# ESP32-S3_4_2_EINK_V1_3.net
KiCad netlist of a schematic drawn in EAGLE
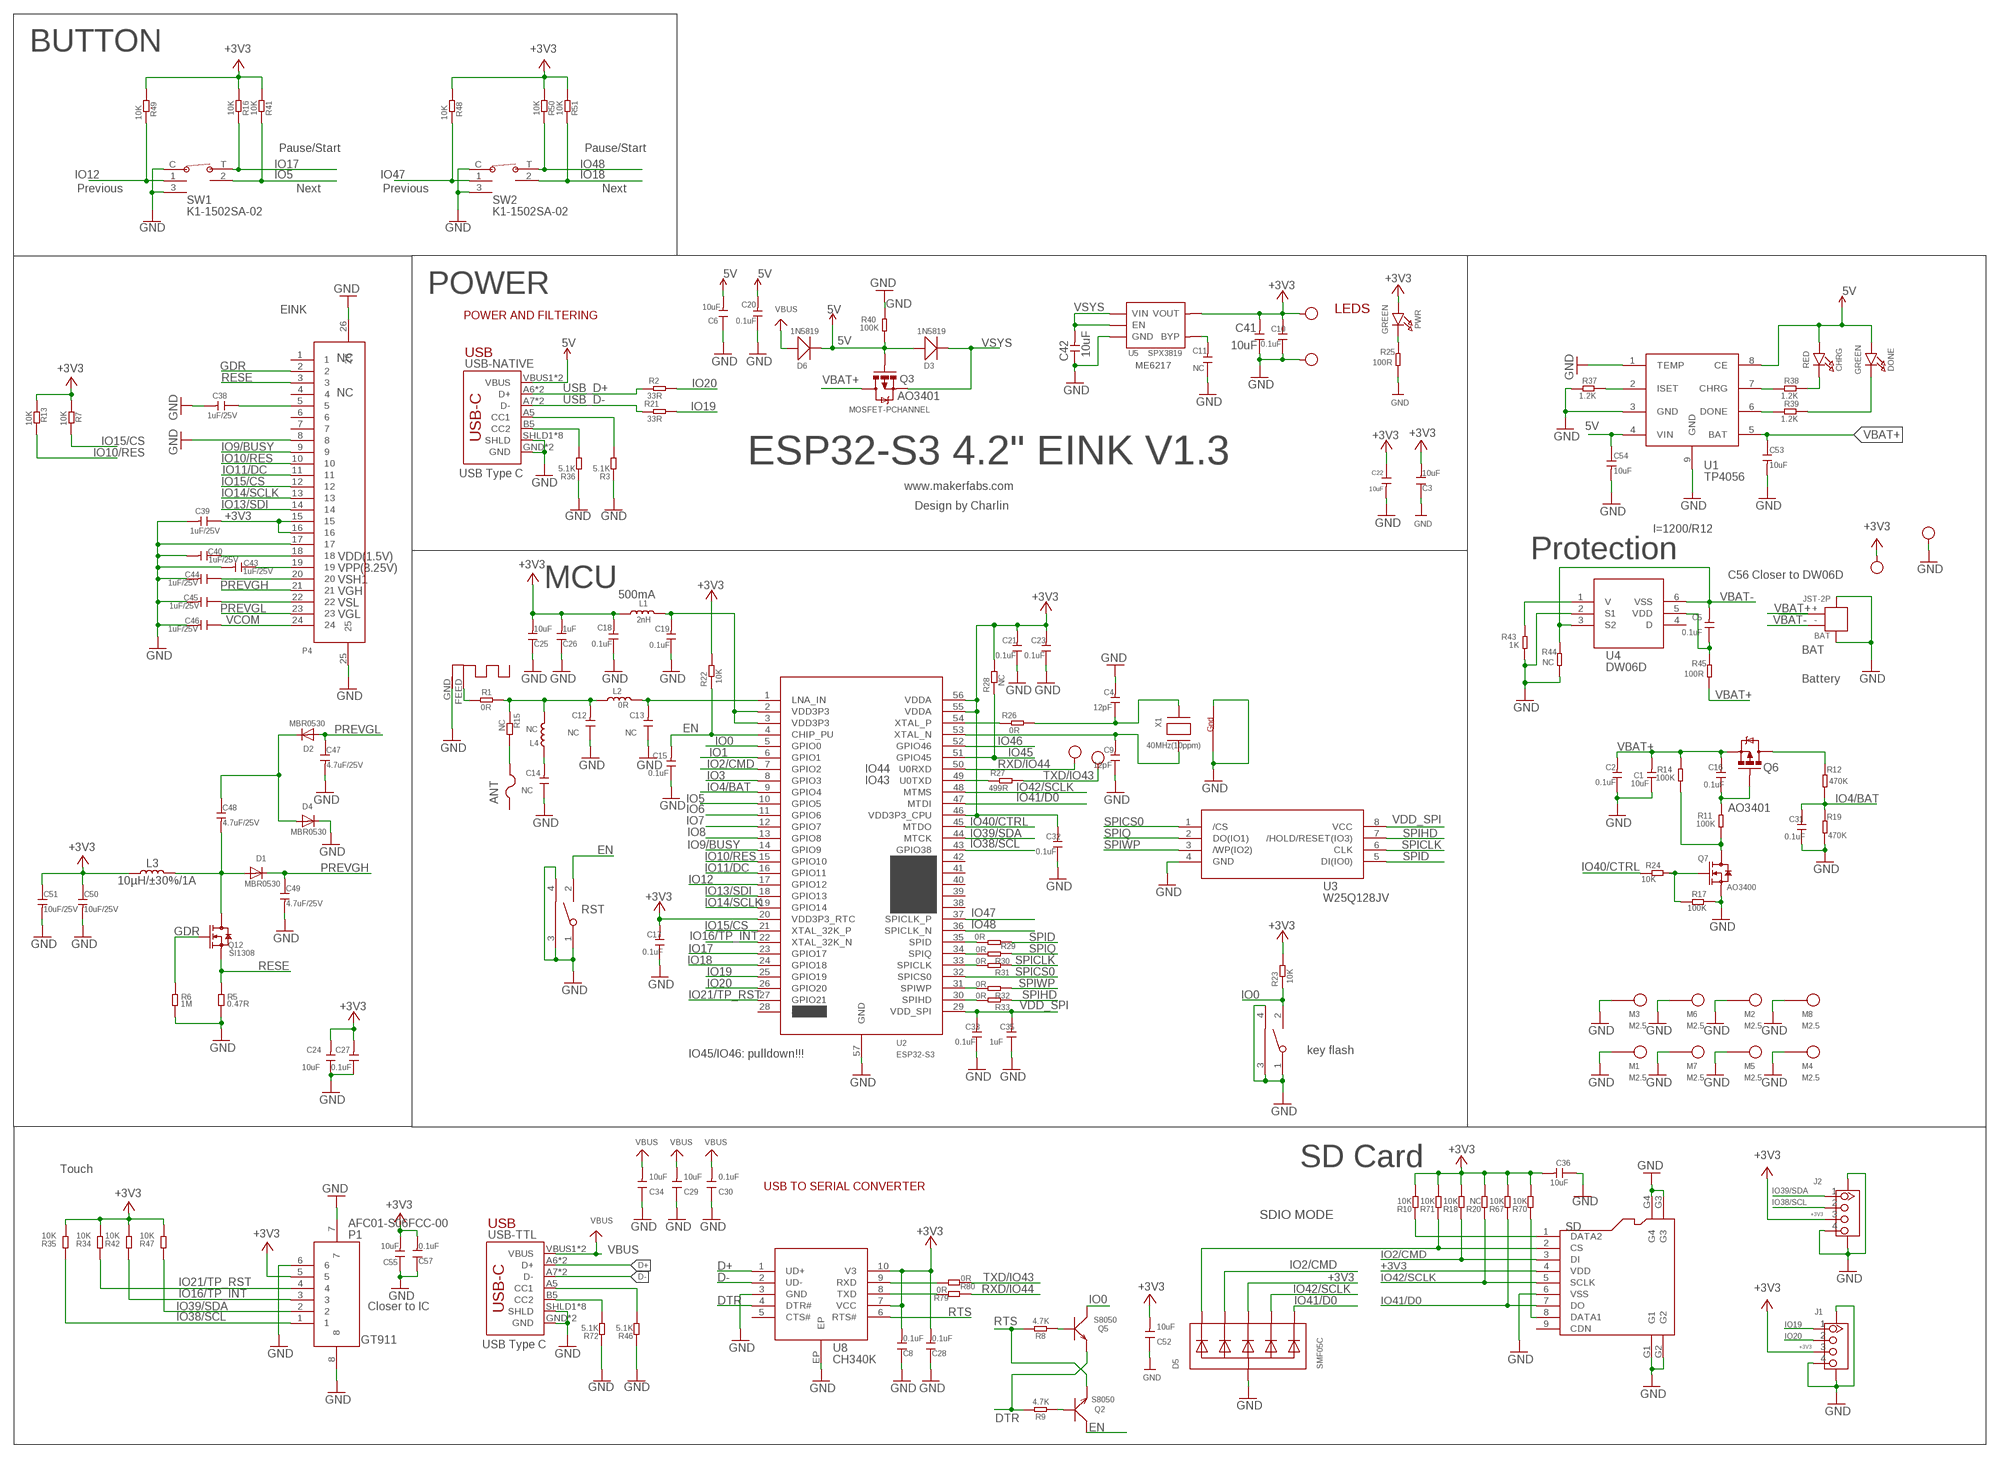
[diagram p0: schematic, sheet 1]

(export (version "E")
  (design (tool "Eeschema 10.0.6"))
  (components
    (comp (ref "3V3")
      (value "TEST-POINT'4545'")
      (footprint "eagle-import:TP-D45MIL")
      (fields (field (name "PARTNO") "DNP") (field (name "PARTNO_1") "DNP"))
      (libsource (lib "eagle-import") (part "TEST-POINT'4545'"))
    )
    (comp (ref "ANT")
      (value "PTCFUSE-1206")
      (footprint "eagle-import:R1206")
      (libsource (lib "eagle-import") (part "PTCFUSE-1206"))
    )
    (comp (ref "ANT1")
      (value "ANTENNA")
      (footprint "eagle-import:RN-ANT")
      (libsource (lib "eagle-import") (part "ANTENNA"))
    )
    (comp (ref "BAT")
      (value "JST-2P")
      (footprint "eagle-import:HW2-SMD-2.0-90D")
      (libsource (lib "eagle-import") (part "JST-2P-SMD'2.0'"))
    )
    (comp (ref "C1")
      (value "10uF")
      (footprint "eagle-import:0603")
      (libsource (lib "eagle-import") (part "C-0603"))
    )
    (comp (ref "C2")
      (value "0.1uF")
      (footprint "eagle-import:0603")
      (libsource (lib "eagle-import") (part "C-0603"))
    )
    (comp (ref "C3")
      (value "10uF")
      (footprint "eagle-import:DISCRETE_C0603")
      (libsource (lib "eagle-import") (part "DISCRETE_C-0603"))
    )
    (comp (ref "C4")
      (value "12pF")
      (footprint "eagle-import:0603")
      (libsource (lib "eagle-import") (part "C-0603"))
    )
    (comp (ref "C5")
      (value "0.1uF")
      (footprint "eagle-import:0603")
      (libsource (lib "eagle-import") (part "C-0603"))
    )
    (comp (ref "C6")
      (value "10uF")
      (footprint "eagle-import:DISCRETE_C0603")
      (libsource (lib "eagle-import") (part "DISCRETE_C-0603"))
    )
    (comp (ref "C8")
      (value "0.1uF")
      (footprint "eagle-import:DISCRETE_C0603")
      (libsource (lib "eagle-import") (part "DISCRETE_C-0603"))
    )
    (comp (ref "C9")
      (value "12pF")
      (footprint "eagle-import:0603")
      (libsource (lib "eagle-import") (part "C-0603"))
    )
    (comp (ref "C10")
      (value "0.1uF")
      (footprint "eagle-import:0603")
      (libsource (lib "eagle-import") (part "C-0603"))
    )
    (comp (ref "C11")
      (value "NC")
      (footprint "eagle-import:0603")
      (libsource (lib "eagle-import") (part "C-0603"))
    )
    (comp (ref "C12")
      (value "NC")
      (footprint "eagle-import:0603")
      (libsource (lib "eagle-import") (part "C-0603"))
    )
    (comp (ref "C13")
      (value "NC")
      (footprint "eagle-import:0603")
      (libsource (lib "eagle-import") (part "C-0603"))
    )
    (comp (ref "C14")
      (value "NC")
      (footprint "eagle-import:0603")
      (libsource (lib "eagle-import") (part "C-0603"))
    )
    (comp (ref "C15")
      (value "0.1uF")
      (footprint "eagle-import:0603")
      (libsource (lib "eagle-import") (part "C-0603"))
    )
    (comp (ref "C16")
      (value "0.1uF")
      (footprint "eagle-import:0603")
      (libsource (lib "eagle-import") (part "C-0603"))
    )
    (comp (ref "C17")
      (value "0.1uF")
      (footprint "eagle-import:0603")
      (libsource (lib "eagle-import") (part "C-0603"))
    )
    (comp (ref "C18")
      (value "0.1uF")
      (footprint "eagle-import:0603")
      (libsource (lib "eagle-import") (part "C-0603"))
    )
    (comp (ref "C19")
      (value "0.1uF")
      (footprint "eagle-import:0603")
      (libsource (lib "eagle-import") (part "C-0603"))
    )
    (comp (ref "C20")
      (value "0.1uF")
      (footprint "eagle-import:0603")
      (libsource (lib "eagle-import") (part "C-0603"))
    )
    (comp (ref "C21")
      (value "0.1uF")
      (footprint "eagle-import:0603")
      (libsource (lib "eagle-import") (part "C-0603"))
    )
    (comp (ref "C22")
      (value "10uF")
      (footprint "eagle-import:0603")
      (libsource (lib "eagle-import") (part "C-0603"))
    )
    (comp (ref "C23")
      (value "0.1uF")
      (footprint "eagle-import:0603")
      (libsource (lib "eagle-import") (part "C-0603"))
    )
    (comp (ref "C24")
      (value "10uF")
      (footprint "eagle-import:0603")
      (libsource (lib "eagle-import") (part "C-0603"))
    )
    (comp (ref "C25")
      (value "10uF")
      (footprint "eagle-import:DISCRETE_C0603")
      (libsource (lib "eagle-import") (part "DISCRETE_C-0603"))
    )
    (comp (ref "C26")
      (value "1uF")
      (footprint "eagle-import:DISCRETE_C0603")
      (libsource (lib "eagle-import") (part "DISCRETE_C-0603"))
    )
    (comp (ref "C27")
      (value "0.1uF")
      (footprint "eagle-import:0603")
      (libsource (lib "eagle-import") (part "C-0603"))
    )
    (comp (ref "C28")
      (value "0.1uF")
      (footprint "eagle-import:DISCRETE_C0603")
      (libsource (lib "eagle-import") (part "DISCRETE_C-0603"))
    )
    (comp (ref "C29")
      (value "10uF")
      (footprint "eagle-import:DISCRETE_C0603")
      (libsource (lib "eagle-import") (part "DISCRETE_C-0603"))
    )
    (comp (ref "C30")
      (value "0.1uF")
      (footprint "eagle-import:DISCRETE_C0603")
      (libsource (lib "eagle-import") (part "DISCRETE_C-0603"))
    )
    (comp (ref "C31")
      (value "0.1uF")
      (footprint "eagle-import:0603")
      (libsource (lib "eagle-import") (part "C-0603"))
    )
    (comp (ref "C32")
      (value "0.1uF")
      (footprint "eagle-import:0603")
      (libsource (lib "eagle-import") (part "C-0603"))
    )
    (comp (ref "C33")
      (value "0.1uF")
      (footprint "eagle-import:0603")
      (libsource (lib "eagle-import") (part "C-0603"))
    )
    (comp (ref "C34")
      (value "10uF")
      (footprint "eagle-import:DISCRETE_C0603")
      (libsource (lib "eagle-import") (part "DISCRETE_C-0603"))
    )
    (comp (ref "C35")
      (value "1uF")
      (footprint "eagle-import:0603")
      (libsource (lib "eagle-import") (part "C-0603"))
    )
    (comp (ref "C36")
      (value "10uF")
      (footprint "eagle-import:DISCRETE_C0603")
      (libsource (lib "eagle-import") (part "DISCRETE_C-0603"))
    )
    (comp (ref "C38")
      (value "1uF/25V")
      (footprint "eagle-import:0603")
      (libsource (lib "eagle-import") (part "C-0603"))
    )
    (comp (ref "C39")
      (value "1uF/25V")
      (footprint "eagle-import:0603")
      (libsource (lib "eagle-import") (part "C-0603"))
    )
    (comp (ref "C40")
      (value "1uF/25V")
      (footprint "eagle-import:0603")
      (libsource (lib "eagle-import") (part "C-0603"))
    )
    (comp (ref "C41")
      (value "10uF")
      (footprint "eagle-import:0603")
      (libsource (lib "eagle-import") (part "C-0603"))
    )
    (comp (ref "C42")
      (value "10uF")
      (footprint "eagle-import:0603")
      (libsource (lib "eagle-import") (part "C-0603"))
    )
    (comp (ref "C43")
      (value "1uF/25V")
      (footprint "eagle-import:0603")
      (libsource (lib "eagle-import") (part "C-0603"))
    )
    (comp (ref "C44")
      (value "1uF/25V")
      (footprint "eagle-import:0603")
      (libsource (lib "eagle-import") (part "C-0603"))
    )
    (comp (ref "C45")
      (value "1uF/25V")
      (footprint "eagle-import:0603")
      (libsource (lib "eagle-import") (part "C-0603"))
    )
    (comp (ref "C46")
      (value "1uF/25V")
      (footprint "eagle-import:0603")
      (libsource (lib "eagle-import") (part "C-0603"))
    )
    (comp (ref "C47")
      (value "4.7uF/25V")
      (footprint "eagle-import:0603")
      (libsource (lib "eagle-import") (part "C-0603"))
    )
    (comp (ref "C48")
      (value "4.7uF/25V")
      (footprint "eagle-import:0603")
      (libsource (lib "eagle-import") (part "C-0603"))
    )
    (comp (ref "C49")
      (value "4.7uF/25V")
      (footprint "eagle-import:0603")
      (libsource (lib "eagle-import") (part "C-0603"))
    )
    (comp (ref "C50")
      (value "10uF/25V")
      (footprint "eagle-import:0603")
      (libsource (lib "eagle-import") (part "C-0603"))
    )
    (comp (ref "C51")
      (value "10uF/25V")
      (footprint "eagle-import:0603")
      (libsource (lib "eagle-import") (part "C-0603"))
    )
    (comp (ref "C52")
      (value "10uF")
      (footprint "eagle-import:DISCRETE_C0603")
      (libsource (lib "eagle-import") (part "DISCRETE_C-0603"))
    )
    (comp (ref "C53")
      (value "10uF")
      (footprint "eagle-import:0603")
      (libsource (lib "eagle-import") (part "C-0603"))
    )
    (comp (ref "C54")
      (value "10uF")
      (footprint "eagle-import:0603")
      (libsource (lib "eagle-import") (part "C-0603"))
    )
    (comp (ref "C55")
      (value "10uF")
      (footprint "eagle-import:DISCRETE_C0603")
      (libsource (lib "eagle-import") (part "DISCRETE_C-0603"))
    )
    (comp (ref "C57")
      (value "0.1uF")
      (footprint "eagle-import:DISCRETE_C0603")
      (libsource (lib "eagle-import") (part "DISCRETE_C-0603"))
    )
    (comp (ref "CHRG")
      (value "RED")
      (footprint "eagle-import:CHIPLED_0805_NOOUTLINE")
      (libsource (lib "eagle-import") (part "LED0805_NOOUTLINE"))
    )
    (comp (ref "D1")
      (value "MBR0530")
      (footprint "eagle-import:SOD-323F")
      (libsource (lib "eagle-import") (part "DIODESOD-323F"))
    )
    (comp (ref "D2")
      (value "MBR0530")
      (footprint "eagle-import:SOD-323F")
      (libsource (lib "eagle-import") (part "DIODESOD-323F"))
    )
    (comp (ref "D3")
      (value "1N5819")
      (footprint "eagle-import:SOD323")
      (libsource (lib "eagle-import") (part "D'0805'"))
    )
    (comp (ref "D4")
      (value "MBR0530")
      (footprint "eagle-import:SOD-323F")
      (libsource (lib "eagle-import") (part "DIODESOD-323F"))
    )
    (comp (ref "D5")
      (value "SMF05C")
      (footprint "eagle-import:SOT363")
      (libsource (lib "eagle-import") (part "TVSARRAY_5LANE"))
    )
    (comp (ref "D6")
      (value "1N5819")
      (footprint "eagle-import:SOD323")
      (libsource (lib "eagle-import") (part "D'0805'"))
    )
    (comp (ref "DONE")
      (value "GREEN")
      (footprint "eagle-import:CHIPLED_0805_NOOUTLINE")
      (libsource (lib "eagle-import") (part "LED0805_NOOUTLINE"))
    )
    (comp (ref "FLASH")
      (value "TS24CA")
      (footprint "eagle-import:2_4_3.5MM")
      (libsource (lib "eagle-import") (part "TS24CA"))
    )
    (comp (ref "G")
      (value "TEST-POINT'4545'")
      (footprint "eagle-import:TP-D45MIL")
      (fields (field (name "PARTNO") "DNP") (field (name "PARTNO_1") "DNP"))
      (libsource (lib "eagle-import") (part "TEST-POINT'4545'"))
    )
    (comp (ref "GND")
      (value "TEST-POINT'4545'")
      (footprint "eagle-import:TP-D45MIL")
      (fields (field (name "PARTNO") "DNP") (field (name "PARTNO_1") "DNP"))
      (libsource (lib "eagle-import") (part "TEST-POINT'4545'"))
    )
    (comp (ref "J1")
      (value "GROVE-CONNECTOR-SMD'90D'")
      (footprint "eagle-import:HW4-SMD-2.0-90D")
      (libsource (lib "eagle-import") (part "GROVE-CONNECTOR-SMD'90D'"))
    )
    (comp (ref "J2")
      (value "GROVE-CONNECTOR-SMD'90D'")
      (footprint "eagle-import:HW4-SMD-2.0-90D")
      (libsource (lib "eagle-import") (part "GROVE-CONNECTOR-SMD'90D'"))
    )
    (comp (ref "L1")
      (value "2nH")
      (footprint "eagle-import:DISCRETE_L0603")
      (libsource (lib "eagle-import") (part "DISCRETE_L0603"))
    )
    (comp (ref "L2")
      (value "0R")
      (footprint "eagle-import:0603")
      (fields (field (name "PROD_ID") "NDUC-07874"))
      (libsource (lib "eagle-import") (part "INDUCTOR-0603-33NH"))
    )
    (comp (ref "L3")
      (value "10µH/±30%/1A")
      (footprint "eagle-import:CR54")
      (fields (field (name "PROD_ID") "NDUC-10789"))
      (libsource (lib "eagle-import") (part "INDUCTOR-CR54-47UH"))
    )
    (comp (ref "L4")
      (value "NC")
      (footprint "eagle-import:0603")
      (fields (field (name "PROD_ID") "NDUC-07874"))
      (libsource (lib "eagle-import") (part "INDUCTOR-0603-33NH"))
    )
    (comp (ref "M1")
      (value "M2.5")
      (footprint "eagle-import:M2.5")
      (libsource (lib "eagle-import") (part "M2.5"))
    )
    (comp (ref "M2")
      (value "M2.5")
      (footprint "eagle-import:M2.5")
      (libsource (lib "eagle-import") (part "M2.5"))
    )
    (comp (ref "M3")
      (value "M2.5")
      (footprint "eagle-import:M2.5")
      (libsource (lib "eagle-import") (part "M2.5"))
    )
    (comp (ref "M4")
      (value "M2.5")
      (footprint "eagle-import:M2.5")
      (libsource (lib "eagle-import") (part "M2.5"))
    )
    (comp (ref "M5")
      (value "M2.5")
      (footprint "eagle-import:M2.5")
      (libsource (lib "eagle-import") (part "M2.5"))
    )
    (comp (ref "M6")
      (value "M2.5")
      (footprint "eagle-import:M2.5")
      (libsource (lib "eagle-import") (part "M2.5"))
    )
    (comp (ref "M7")
      (value "M2.5")
      (footprint "eagle-import:M2.5")
      (libsource (lib "eagle-import") (part "M2.5"))
    )
    (comp (ref "M8")
      (value "M2.5")
      (footprint "eagle-import:M2.5")
      (libsource (lib "eagle-import") (part "M2.5"))
    )
    (comp (ref "P1")
      (value "AFC01-S06FCC-00")
      (footprint "eagle-import:SMD8-50P-740L535W")
      (libsource (lib "eagle-import") (part "AFC01-S06FCC-00"))
    )
    (comp (ref "P4")
      (value "FPC-24P")
      (footprint "eagle-import:SMD26-50P-1760L450W")
      (libsource (lib "eagle-import") (part "FPC-24P"))
    )
    (comp (ref "PWR")
      (value "GREEN")
      (footprint "eagle-import:CHIPLED_0805_NOOUTLINE")
      (libsource (lib "eagle-import") (part "LED0805_NOOUTLINE"))
    )
    (comp (ref "Q2")
      (value "S8050")
      (footprint "eagle-import:SOT23")
      (libsource (lib "eagle-import") (part "TRANSISTOR-NPN-SOT23"))
    )
    (comp (ref "Q3")
      (value "MOSFET-PCHANNEL")
      (footprint "eagle-import:SOT23-3")
      (libsource (lib "eagle-import") (part "MOSFET-PCHANNEL"))
    )
    (comp (ref "Q5")
      (value "S8050")
      (footprint "eagle-import:SOT23")
      (libsource (lib "eagle-import") (part "TRANSISTOR-NPN-SOT23"))
    )
    (comp (ref "Q6")
      (value "MOSFET-PCHANNEL")
      (footprint "eagle-import:SOT23-3")
      (libsource (lib "eagle-import") (part "MOSFET-PCHANNEL"))
    )
    (comp (ref "Q7")
      (value "AO3400")
      (footprint "eagle-import:DISCRETE_SOT23")
      (libsource (lib "eagle-import") (part "DISCRETE_MOSFET-NSOT23"))
    )
    (comp (ref "Q12")
      (value "SI1308")
      (footprint "eagle-import:SOT23")
      (libsource (lib "eagle-import") (part "MOSFET-N'SOT23'"))
    )
    (comp (ref "R1")
      (value "0R")
      (footprint "eagle-import:R0603")
      (libsource (lib "eagle-import") (part "R-0603"))
    )
    (comp (ref "R2")
      (value "33R")
      (footprint "eagle-import:R0603")
      (libsource (lib "eagle-import") (part "R-0603"))
    )
    (comp (ref "R3")
      (value "5.1K")
      (footprint "eagle-import:DISCRETE_R0603")
      (libsource (lib "eagle-import") (part "DISCRETE_R-0603"))
    )
    (comp (ref "R5")
      (value "0.47R")
      (footprint "eagle-import:R0603")
      (libsource (lib "eagle-import") (part "R-0603"))
    )
    (comp (ref "R6")
      (value "1M")
      (footprint "eagle-import:R0603")
      (libsource (lib "eagle-import") (part "R-0603"))
    )
    (comp (ref "R7")
      (value "10K")
      (footprint "eagle-import:R0603")
      (libsource (lib "eagle-import") (part "R-0603"))
    )
    (comp (ref "R8")
      (value "4.7K")
      (footprint "eagle-import:R0603")
      (libsource (lib "eagle-import") (part "R-0603"))
    )
    (comp (ref "R9")
      (value "4.7K")
      (footprint "eagle-import:R0603")
      (libsource (lib "eagle-import") (part "R-0603"))
    )
    (comp (ref "R10")
      (value "10K")
      (footprint "eagle-import:DISCRETE_R0603")
      (libsource (lib "eagle-import") (part "DISCRETE_R-0603"))
    )
    (comp (ref "R11")
      (value "100K")
      (footprint "eagle-import:R0603")
      (libsource (lib "eagle-import") (part "R-0603"))
    )
    (comp (ref "R12")
      (value "470K")
      (footprint "eagle-import:R0603")
      (libsource (lib "eagle-import") (part "R-0603"))
    )
    (comp (ref "R13")
      (value "10K")
      (footprint "eagle-import:R0603")
      (libsource (lib "eagle-import") (part "R-0603"))
    )
    (comp (ref "R14")
      (value "100K")
      (footprint "eagle-import:R0603")
      (libsource (lib "eagle-import") (part "R-0603"))
    )
    (comp (ref "R15")
      (value "NC")
      (footprint "eagle-import:R0603")
      (libsource (lib "eagle-import") (part "R-0603"))
    )
    (comp (ref "R16")
      (value "10K")
      (footprint "eagle-import:R0603")
      (libsource (lib "eagle-import") (part "R-0603"))
    )
    (comp (ref "R17")
      (value "100K")
      (footprint "eagle-import:R0603")
      (libsource (lib "eagle-import") (part "R-0603"))
    )
    (comp (ref "R18")
      (value "10K")
      (footprint "eagle-import:DISCRETE_R0603")
      (libsource (lib "eagle-import") (part "DISCRETE_R-0603"))
    )
    (comp (ref "R19")
      (value "470K")
      (footprint "eagle-import:R0603")
      (libsource (lib "eagle-import") (part "R-0603"))
    )
    (comp (ref "R20")
      (value "NC")
      (footprint "eagle-import:DISCRETE_R0603")
      (libsource (lib "eagle-import") (part "DISCRETE_R-0603"))
    )
    (comp (ref "R21")
      (value "33R")
      (footprint "eagle-import:R0603")
      (libsource (lib "eagle-import") (part "R-0603"))
    )
    (comp (ref "R22")
      (value "10K")
      (footprint "eagle-import:R0603")
      (libsource (lib "eagle-import") (part "R-0603"))
    )
    (comp (ref "R23")
      (value "10K")
      (footprint "eagle-import:R0603")
      (libsource (lib "eagle-import") (part "R-0603"))
    )
    (comp (ref "R24")
      (value "10K")
      (footprint "eagle-import:R0603")
      (libsource (lib "eagle-import") (part "R-0603"))
    )
    (comp (ref "R25")
      (value "100R")
      (footprint "eagle-import:R0603")
      (libsource (lib "eagle-import") (part "R-0603"))
    )
    (comp (ref "R26")
      (value "0R")
      (footprint "eagle-import:R0603")
      (libsource (lib "eagle-import") (part "R-0603"))
    )
    (comp (ref "R27")
      (value "499R")
      (footprint "eagle-import:R0603")
      (libsource (lib "eagle-import") (part "R-0603"))
    )
    (comp (ref "R28")
      (value "NC")
      (footprint "eagle-import:R0603")
      (libsource (lib "eagle-import") (part "R-0603"))
    )
    (comp (ref "R29")
      (value "0R")
      (footprint "eagle-import:R0603")
      (libsource (lib "eagle-import") (part "R-0603"))
    )
    (comp (ref "R30")
      (value "0R")
      (footprint "eagle-import:R0603")
      (libsource (lib "eagle-import") (part "R-0603"))
    )
    (comp (ref "R31")
      (value "0R")
      (footprint "eagle-import:R0603")
      (libsource (lib "eagle-import") (part "R-0603"))
    )
    (comp (ref "R32")
      (value "0R")
      (footprint "eagle-import:R0603")
      (libsource (lib "eagle-import") (part "R-0603"))
    )
    (comp (ref "R33")
      (value "0R")
      (footprint "eagle-import:R0603")
      (libsource (lib "eagle-import") (part "R-0603"))
    )
    (comp (ref "R34")
      (value "10K")
      (footprint "eagle-import:DISCRETE_R0603")
      (libsource (lib "eagle-import") (part "DISCRETE_R-0603"))
    )
    (comp (ref "R35")
      (value "10K")
      (footprint "eagle-import:DISCRETE_R0603")
      (libsource (lib "eagle-import") (part "DISCRETE_R-0603"))
    )
    (comp (ref "R36")
      (value "5.1K")
      (footprint "eagle-import:DISCRETE_R0603")
      (libsource (lib "eagle-import") (part "DISCRETE_R-0603"))
    )
    (comp (ref "R37")
      (value "1.2K")
      (footprint "eagle-import:R0603")
      (libsource (lib "eagle-import") (part "R-0603"))
    )
    (comp (ref "R38")
      (value "1.2K")
      (footprint "eagle-import:R0603")
      (libsource (lib "eagle-import") (part "R-0603"))
    )
    (comp (ref "R39")
      (value "1.2K")
      (footprint "eagle-import:R0603")
      (libsource (lib "eagle-import") (part "R-0603"))
    )
    (comp (ref "R40")
      (value "100K")
      (footprint "eagle-import:R0603")
      (libsource (lib "eagle-import") (part "R-0603"))
    )
    (comp (ref "R41")
      (value "10K")
      (footprint "eagle-import:R0603")
      (libsource (lib "eagle-import") (part "R-0603"))
    )
    (comp (ref "R42")
      (value "10K")
      (footprint "eagle-import:DISCRETE_R0603")
      (libsource (lib "eagle-import") (part "DISCRETE_R-0603"))
    )
    (comp (ref "R43")
      (value "1K")
      (footprint "eagle-import:R0603")
      (libsource (lib "eagle-import") (part "R-0603"))
    )
    (comp (ref "R44")
      (value "NC")
      (footprint "eagle-import:R0603")
      (libsource (lib "eagle-import") (part "R-0603"))
    )
    (comp (ref "R45")
      (value "100R")
      (footprint "eagle-import:R0603")
      (libsource (lib "eagle-import") (part "R-0603"))
    )
    (comp (ref "R46")
      (value "5.1K")
      (footprint "eagle-import:DISCRETE_R0603")
      (libsource (lib "eagle-import") (part "DISCRETE_R-0603"))
    )
    (comp (ref "R47")
      (value "10K")
      (footprint "eagle-import:DISCRETE_R0603")
      (libsource (lib "eagle-import") (part "DISCRETE_R-0603"))
    )
    (comp (ref "R48")
      (value "10K")
      (footprint "eagle-import:R0603")
      (libsource (lib "eagle-import") (part "R-0603"))
    )
    (comp (ref "R49")
      (value "10K")
      (footprint "eagle-import:R0603")
      (libsource (lib "eagle-import") (part "R-0603"))
    )
    (comp (ref "R50")
      (value "10K")
      (footprint "eagle-import:R0603")
      (libsource (lib "eagle-import") (part "R-0603"))
    )
    (comp (ref "R51")
      (value "10K")
      (footprint "eagle-import:R0603")
      (libsource (lib "eagle-import") (part "R-0603"))
    )
    (comp (ref "R67")
      (value "10K")
      (footprint "eagle-import:DISCRETE_R0603")
      (libsource (lib "eagle-import") (part "DISCRETE_R-0603"))
    )
    (comp (ref "R70")
      (value "10K")
      (footprint "eagle-import:DISCRETE_R0603")
      (libsource (lib "eagle-import") (part "DISCRETE_R-0603"))
    )
    (comp (ref "R71")
      (value "10K")
      (footprint "eagle-import:DISCRETE_R0603")
      (libsource (lib "eagle-import") (part "DISCRETE_R-0603"))
    )
    (comp (ref "R72")
      (value "5.1K")
      (footprint "eagle-import:DISCRETE_R0603")
      (libsource (lib "eagle-import") (part "DISCRETE_R-0603"))
    )
    (comp (ref "R79")
      (value "0R")
      (footprint "eagle-import:R0603")
      (libsource (lib "eagle-import") (part "R-0603"))
    )
    (comp (ref "R80")
      (value "0R")
      (footprint "eagle-import:R0603")
      (libsource (lib "eagle-import") (part "R-0603"))
    )
    (comp (ref "RST")
      (value "TS24CA")
      (footprint "eagle-import:2_4_3.5MM")
      (libsource (lib "eagle-import") (part "TS24CA"))
    )
    (comp (ref "RX")
      (value "TEST-POINT'4545'")
      (footprint "eagle-import:TP-D45MIL")
      (fields (field (name "PARTNO") "DNP") (field (name "PARTNO_1") "DNP"))
      (libsource (lib "eagle-import") (part "TEST-POINT'4545'"))
    )
    (comp (ref "SD")
      (value "HOLDER-MICROSD-9P")
      (footprint "eagle-import:9P-SMD-W_-RING")
      (libsource (lib "eagle-import") (part "HOLDER-MICROSD-9P"))
    )
    (comp (ref "SW1")
      (value "K1-1502SA-02")
      (footprint "eagle-import:SMD5-60P-1180L1170W")
      (libsource (lib "eagle-import") (part "K1-1502SA-02"))
    )
    (comp (ref "SW2")
      (value "K1-1502SA-02")
      (footprint "eagle-import:SMD5-60P-1180L1170W")
      (libsource (lib "eagle-import") (part "K1-1502SA-02"))
    )
    (comp (ref "TX")
      (value "TEST-POINT'4545'")
      (footprint "eagle-import:TP-D45MIL")
      (fields (field (name "PARTNO") "DNP") (field (name "PARTNO_1") "DNP"))
      (libsource (lib "eagle-import") (part "TEST-POINT'4545'"))
    )
    (comp (ref "U1")
      (value "TP4056")
      (footprint "eagle-import:SOP8-1.27P")
      (libsource (lib "eagle-import") (part "TP4056"))
    )
    (comp (ref "U2")
      (value "ESP32-S3")
      (footprint "eagle-import:QFN56-7_7MM")
      (libsource (lib "eagle-import") (part "ESP32-S3"))
    )
    (comp (ref "U3")
      (value "W25Q128JV")
      (footprint "eagle-import:SOIC-8-208MIL")
      (libsource (lib "eagle-import") (part "W25Q128JV"))
    )
    (comp (ref "U4")
      (value "DW06D")
      (footprint "eagle-import:SOT-23-6")
      (libsource (lib "eagle-import") (part "DW06D"))
    )
    (comp (ref "U5")
      (value "SPX3819")
      (footprint "eagle-import:SOT23-5")
      (libsource (lib "eagle-import") (part "SPX3819"))
    )
    (comp (ref "U8")
      (value "CH340K")
      (footprint "eagle-import:ESOP-10-EP-150MIL")
      (libsource (lib "eagle-import") (part "CH340K"))
    )
    (comp (ref "USB-NATIVE")
      (value "USB_C5")
      (footprint "eagle-import:USB-C-16P-5")
      (libsource (lib "eagle-import") (part "USB_C5"))
    )
    (comp (ref "USB-TTL")
      (value "USB_C5")
      (footprint "eagle-import:USB-C-16P-5")
      (libsource (lib "eagle-import") (part "USB_C5"))
    )
    (comp (ref "V")
      (value "TEST-POINT'4545'")
      (footprint "eagle-import:TP-D45MIL")
      (fields (field (name "PARTNO") "DNP") (field (name "PARTNO_1") "DNP"))
      (libsource (lib "eagle-import") (part "TEST-POINT'4545'"))
    )
    (comp (ref "X1")
      (value "40MHz(10ppm)")
      (footprint "eagle-import:NX3225")
      (libsource (lib "eagle-import") (part "XTAL-4-3225"))
    )
  )
  (nets
    (net (code "1") (name "+3V3") (class "Default")
      (node (ref "3V3") (pin "T") (pinfunction "T_T") (pintype "bidirectional"))
      (node (ref "C10") (pin "2") (pinfunction "2_2") (pintype "passive"))
      (node (ref "C17") (pin "2") (pinfunction "2_2") (pintype "passive"))
      (node (ref "C18") (pin "2") (pinfunction "2_2") (pintype "passive"))
      (node (ref "C21") (pin "2") (pinfunction "2_2") (pintype "passive"))
      (node (ref "C22") (pin "1") (pinfunction "1_1") (pintype "passive"))
      (node (ref "C23") (pin "2") (pinfunction "2_2") (pintype "passive"))
      (node (ref "C24") (pin "2") (pinfunction "2_2") (pintype "passive"))
      (node (ref "C25") (pin "2") (pinfunction "2_2") (pintype "passive"))
      (node (ref "C26") (pin "2") (pinfunction "2_2") (pintype "passive"))
      (node (ref "C27") (pin "2") (pinfunction "2_2") (pintype "passive"))
      (node (ref "C28") (pin "2") (pinfunction "2_2") (pintype "passive"))
      (node (ref "C3") (pin "2") (pinfunction "2_2") (pintype "passive"))
      (node (ref "C32") (pin "2") (pinfunction "2_2") (pintype "passive"))
      (node (ref "C36") (pin "2") (pinfunction "2_2") (pintype "passive"))
      (node (ref "C39") (pin "1") (pinfunction "1_1") (pintype "passive"))
      (node (ref "C41") (pin "2") (pinfunction "2_2") (pintype "passive"))
      (node (ref "C50") (pin "1") (pinfunction "1_1") (pintype "passive"))
      (node (ref "C51") (pin "1") (pinfunction "1_1") (pintype "passive"))
      (node (ref "C52") (pin "2") (pinfunction "2_2") (pintype "passive"))
      (node (ref "C55") (pin "2") (pinfunction "2_2") (pintype "passive"))
      (node (ref "C57") (pin "2") (pinfunction "2_2") (pintype "passive"))
      (node (ref "C8") (pin "2") (pinfunction "2_2") (pintype "passive"))
      (node (ref "D5") (pin "4") (pinfunction "C3_4") (pintype "passive"))
      (node (ref "J1") (pin "3") (pinfunction "3_3") (pintype "bidirectional"))
      (node (ref "J2") (pin "3") (pinfunction "3_3") (pintype "bidirectional"))
      (node (ref "L1") (pin "1") (pinfunction "1_1") (pintype "passive"))
      (node (ref "L3") (pin "P$1") (pinfunction "1_P$1") (pintype "passive"))
      (node (ref "P1") (pin "5") (pinfunction "5_5") (pintype "bidirectional"))
      (node (ref "P4") (pin "15") (pinfunction "15_15") (pintype "bidirectional"))
      (node (ref "P4") (pin "16") (pinfunction "16_16") (pintype "bidirectional"))
      (node (ref "PWR") (pin "A") (pinfunction "A_A") (pintype "passive"))
      (node (ref "R10") (pin "2") (pinfunction "2_2") (pintype "passive"))
      (node (ref "R13") (pin "1") (pinfunction "1_1") (pintype "passive"))
      (node (ref "R16") (pin "1") (pinfunction "1_1") (pintype "passive"))
      (node (ref "R18") (pin "2") (pinfunction "2_2") (pintype "passive"))
      (node (ref "R20") (pin "2") (pinfunction "2_2") (pintype "passive"))
      (node (ref "R22") (pin "2") (pinfunction "2_2") (pintype "passive"))
      (node (ref "R23") (pin "2") (pinfunction "2_2") (pintype "passive"))
      (node (ref "R28") (pin "2") (pinfunction "2_2") (pintype "passive"))
      (node (ref "R34") (pin "2") (pinfunction "2_2") (pintype "passive"))
      (node (ref "R35") (pin "2") (pinfunction "2_2") (pintype "passive"))
      (node (ref "R41") (pin "1") (pinfunction "1_1") (pintype "passive"))
      (node (ref "R42") (pin "2") (pinfunction "2_2") (pintype "passive"))
      (node (ref "R47") (pin "2") (pinfunction "2_2") (pintype "passive"))
      (node (ref "R48") (pin "1") (pinfunction "1_1") (pintype "passive"))
      (node (ref "R49") (pin "1") (pinfunction "1_1") (pintype "passive"))
      (node (ref "R50") (pin "1") (pinfunction "1_1") (pintype "passive"))
      (node (ref "R51") (pin "1") (pinfunction "1_1") (pintype "passive"))
      (node (ref "R67") (pin "2") (pinfunction "2_2") (pintype "passive"))
      (node (ref "R7") (pin "1") (pinfunction "1_1") (pintype "passive"))
      (node (ref "R70") (pin "2") (pinfunction "2_2") (pintype "passive"))
      (node (ref "R71") (pin "2") (pinfunction "2_2") (pintype "passive"))
      (node (ref "SD") (pin "4") (pinfunction "VDD_4") (pintype "bidirectional"))
      (node (ref "U2") (pin "20") (pinfunction "VDD3P3_RTC_20") (pintype "bidirectional"))
      (node (ref "U2") (pin "46") (pinfunction "VDD3P3_CPU_46") (pintype "bidirectional"))
      (node (ref "U2") (pin "55") (pinfunction "VDDA_55") (pintype "bidirectional"))
      (node (ref "U2") (pin "56") (pinfunction "VDDA_56") (pintype "bidirectional"))
      (node (ref "U5") (pin "5") (pinfunction "VOUT_5") (pintype "bidirectional"))
      (node (ref "U8") (pin "10") (pinfunction "V3_10") (pintype "bidirectional"))
      (node (ref "U8") (pin "7") (pinfunction "VCC_7") (pintype "bidirectional"))
      (node (ref "V") (pin "T") (pinfunction "T_T") (pintype "bidirectional"))
    )
    (net (code "2") (name "/DTR") (class "Default")
      (node (ref "Q5") (pin "2") (pinfunction "E_2") (pintype "passive"))
      (node (ref "R9") (pin "2") (pinfunction "2_2") (pintype "passive"))
      (node (ref "U8") (pin "4") (pinfunction "DTR#_4") (pintype "bidirectional"))
    )
    (net (code "3") (name "/EN") (class "Default")
      (node (ref "C15") (pin "2") (pinfunction "2_2") (pintype "passive"))
      (node (ref "Q2") (pin "3") (pinfunction "C_3") (pintype "passive"))
      (node (ref "R22") (pin "1") (pinfunction "1_1") (pintype "passive"))
      (node (ref "RST") (pin "2") (pinfunction "2_2") (pintype "bidirectional"))
      (node (ref "U2") (pin "4") (pinfunction "CHIP_PU_4") (pintype "bidirectional"))
    )
    (net (code "4") (name "/GDR") (class "Default")
      (node (ref "P4") (pin "2") (pinfunction "2_2") (pintype "bidirectional"))
      (node (ref "Q12") (pin "1") (pinfunction "G_1") (pintype "passive"))
      (node (ref "R6") (pin "1") (pinfunction "1_1") (pintype "passive"))
    )
    (net (code "5") (name "/IO0") (class "Default")
      (node (ref "FLASH") (pin "2") (pinfunction "2_2") (pintype "bidirectional"))
      (node (ref "Q5") (pin "3") (pinfunction "C_3") (pintype "passive"))
      (node (ref "R23") (pin "1") (pinfunction "1_1") (pintype "passive"))
      (node (ref "U2") (pin "5") (pinfunction "GPIO0_5") (pintype "bidirectional"))
    )
    (net (code "6") (name "/IO1") (class "Default")
      (node (ref "U2") (pin "6") (pinfunction "GPIO1_6") (pintype "bidirectional"))
    )
    (net (code "7") (name "/IO2{slash}CMD") (class "Default")
      (node (ref "D5") (pin "3") (pinfunction "C2_3") (pintype "passive"))
      (node (ref "R18") (pin "1") (pinfunction "1_1") (pintype "passive"))
      (node (ref "SD") (pin "3") (pinfunction "DI_3") (pintype "bidirectional"))
      (node (ref "U2") (pin "7") (pinfunction "GPIO2_7") (pintype "bidirectional"))
    )
    (net (code "8") (name "/IO3") (class "Default")
      (node (ref "U2") (pin "8") (pinfunction "GPIO3_8") (pintype "bidirectional"))
    )
    (net (code "9") (name "/IO4{slash}BAT") (class "Default")
      (node (ref "C31") (pin "2") (pinfunction "2_2") (pintype "passive"))
      (node (ref "R12") (pin "1") (pinfunction "1_1") (pintype "passive"))
      (node (ref "R19") (pin "2") (pinfunction "2_2") (pintype "passive"))
      (node (ref "U2") (pin "9") (pinfunction "GPIO4_9") (pintype "bidirectional"))
    )
    (net (code "10") (name "/IO5") (class "Default")
      (node (ref "R41") (pin "2") (pinfunction "2_2") (pintype "passive"))
      (node (ref "SW1") (pin "2") (pinfunction "2_2") (pintype "bidirectional"))
      (node (ref "U2") (pin "10") (pinfunction "GPIO5_10") (pintype "bidirectional"))
    )
    (net (code "11") (name "/IO6") (class "Default")
      (node (ref "U2") (pin "11") (pinfunction "GPIO6_11") (pintype "bidirectional"))
    )
    (net (code "12") (name "/IO7") (class "Default")
      (node (ref "U2") (pin "12") (pinfunction "GPIO7_12") (pintype "bidirectional"))
    )
    (net (code "13") (name "/IO8") (class "Default")
      (node (ref "U2") (pin "13") (pinfunction "GPIO8_13") (pintype "bidirectional"))
    )
    (net (code "14") (name "/IO9{slash}BUSY") (class "Default")
      (node (ref "P4") (pin "9") (pinfunction "9_9") (pintype "bidirectional"))
      (node (ref "U2") (pin "14") (pinfunction "GPIO9_14") (pintype "bidirectional"))
    )
    (net (code "15") (name "/IO10{slash}RES") (class "Default")
      (node (ref "P4") (pin "10") (pinfunction "10_10") (pintype "bidirectional"))
      (node (ref "R13") (pin "2") (pinfunction "2_2") (pintype "passive"))
      (node (ref "U2") (pin "15") (pinfunction "GPIO10_15") (pintype "bidirectional"))
    )
    (net (code "16") (name "/IO11{slash}DC") (class "Default")
      (node (ref "P4") (pin "11") (pinfunction "11_11") (pintype "bidirectional"))
      (node (ref "U2") (pin "16") (pinfunction "GPIO11_16") (pintype "bidirectional"))
    )
    (net (code "17") (name "/IO12") (class "Default")
      (node (ref "R49") (pin "2") (pinfunction "2_2") (pintype "passive"))
      (node (ref "SW1") (pin "1") (pinfunction "1_1") (pintype "bidirectional"))
      (node (ref "U2") (pin "17") (pinfunction "GPIO12_17") (pintype "bidirectional"))
    )
    (net (code "18") (name "/IO13{slash}SDI") (class "Default")
      (node (ref "P4") (pin "14") (pinfunction "14_14") (pintype "bidirectional"))
      (node (ref "U2") (pin "18") (pinfunction "GPIO13_18") (pintype "bidirectional"))
    )
    (net (code "19") (name "/IO14{slash}SCLK") (class "Default")
      (node (ref "P4") (pin "13") (pinfunction "13_13") (pintype "bidirectional"))
      (node (ref "U2") (pin "19") (pinfunction "GPIO14_19") (pintype "bidirectional"))
    )
    (net (code "20") (name "/IO15{slash}CS") (class "Default")
      (node (ref "P4") (pin "12") (pinfunction "12_12") (pintype "bidirectional"))
      (node (ref "R7") (pin "2") (pinfunction "2_2") (pintype "passive"))
      (node (ref "U2") (pin "21") (pinfunction "XTAL_32K_P_21") (pintype "bidirectional"))
    )
    (net (code "21") (name "/IO16{slash}TP_INT") (class "Default")
      (node (ref "P1") (pin "3") (pinfunction "3_3") (pintype "bidirectional"))
      (node (ref "R42") (pin "1") (pinfunction "1_1") (pintype "passive"))
      (node (ref "U2") (pin "22") (pinfunction "XTAL_32K_N_22") (pintype "bidirectional"))
    )
    (net (code "22") (name "/IO17") (class "Default")
      (node (ref "R16") (pin "2") (pinfunction "2_2") (pintype "passive"))
      (node (ref "SW1") (pin "T") (pinfunction "T_T") (pintype "bidirectional"))
      (node (ref "U2") (pin "23") (pinfunction "GPIO17_23") (pintype "bidirectional"))
    )
    (net (code "23") (name "/IO18") (class "Default")
      (node (ref "R51") (pin "2") (pinfunction "2_2") (pintype "passive"))
      (node (ref "SW2") (pin "2") (pinfunction "2_2") (pintype "bidirectional"))
      (node (ref "U2") (pin "24") (pinfunction "GPIO18_24") (pintype "bidirectional"))
    )
    (net (code "24") (name "/IO19") (class "Default")
      (node (ref "J1") (pin "1") (pinfunction "1_1") (pintype "bidirectional"))
      (node (ref "R21") (pin "2") (pinfunction "2_2") (pintype "passive"))
      (node (ref "U2") (pin "25") (pinfunction "GPIO19_25") (pintype "bidirectional"))
    )
    (net (code "25") (name "/IO20") (class "Default")
      (node (ref "J1") (pin "2") (pinfunction "2_2") (pintype "bidirectional"))
      (node (ref "R2") (pin "2") (pinfunction "2_2") (pintype "passive"))
      (node (ref "U2") (pin "26") (pinfunction "GPIO20_26") (pintype "bidirectional"))
    )
    (net (code "26") (name "/IO21{slash}TP_RST") (class "Default")
      (node (ref "P1") (pin "4") (pinfunction "4_4") (pintype "bidirectional"))
      (node (ref "R34") (pin "1") (pinfunction "1_1") (pintype "passive"))
      (node (ref "U2") (pin "27") (pinfunction "GPIO21_27") (pintype "bidirectional"))
    )
    (net (code "27") (name "/IO38{slash}SCL") (class "Default")
      (node (ref "J2") (pin "2") (pinfunction "2_2") (pintype "bidirectional"))
      (node (ref "P1") (pin "1") (pinfunction "1_1") (pintype "bidirectional"))
      (node (ref "R35") (pin "1") (pinfunction "1_1") (pintype "passive"))
      (node (ref "U2") (pin "43") (pinfunction "GPIO38_43") (pintype "bidirectional"))
    )
    (net (code "28") (name "/IO39{slash}SDA") (class "Default")
      (node (ref "J2") (pin "1") (pinfunction "1_1") (pintype "bidirectional"))
      (node (ref "P1") (pin "2") (pinfunction "2_2") (pintype "bidirectional"))
      (node (ref "R47") (pin "1") (pinfunction "1_1") (pintype "passive"))
      (node (ref "U2") (pin "44") (pinfunction "MTCK_44") (pintype "bidirectional"))
    )
    (net (code "29") (name "/IO40{slash}CTRL") (class "Default")
      (node (ref "R24") (pin "2") (pinfunction "2_2") (pintype "passive"))
      (node (ref "U2") (pin "45") (pinfunction "MTDO_45") (pintype "bidirectional"))
    )
    (net (code "30") (name "/IO41{slash}D0") (class "Default")
      (node (ref "D5") (pin "6") (pinfunction "C5_6") (pintype "passive"))
      (node (ref "R67") (pin "1") (pinfunction "1_1") (pintype "passive"))
      (node (ref "SD") (pin "7") (pinfunction "DO_7") (pintype "bidirectional"))
      (node (ref "U2") (pin "47") (pinfunction "MTDI_47") (pintype "bidirectional"))
    )
    (net (code "31") (name "/IO42{slash}SCLK") (class "Default")
      (node (ref "D5") (pin "5") (pinfunction "C4_5") (pintype "passive"))
      (node (ref "R20") (pin "1") (pinfunction "1_1") (pintype "passive"))
      (node (ref "SD") (pin "5") (pinfunction "SCLK_5") (pintype "bidirectional"))
      (node (ref "U2") (pin "48") (pinfunction "MTMS_48") (pintype "bidirectional"))
    )
    (net (code "32") (name "/IO45") (class "Default")
      (node (ref "R28") (pin "1") (pinfunction "1_1") (pintype "passive"))
      (node (ref "U2") (pin "51") (pinfunction "GPIO45_51") (pintype "bidirectional"))
    )
    (net (code "33") (name "/IO46") (class "Default")
      (node (ref "U2") (pin "52") (pinfunction "GPIO46_52") (pintype "bidirectional"))
    )
    (net (code "34") (name "/IO47") (class "Default")
      (node (ref "R48") (pin "2") (pinfunction "2_2") (pintype "passive"))
      (node (ref "SW2") (pin "1") (pinfunction "1_1") (pintype "bidirectional"))
      (node (ref "U2") (pin "37") (pinfunction "SPICLK_P_37") (pintype "bidirectional"))
    )
    (net (code "35") (name "/IO48") (class "Default")
      (node (ref "R50") (pin "2") (pinfunction "2_2") (pintype "passive"))
      (node (ref "SW2") (pin "T") (pinfunction "T_T") (pintype "bidirectional"))
      (node (ref "U2") (pin "36") (pinfunction "SPICLK_N_36") (pintype "bidirectional"))
    )
    (net (code "36") (name "/PREVGH") (class "Default")
      (node (ref "C49") (pin "1") (pinfunction "1_1") (pintype "passive"))
      (node (ref "D1") (pin "C") (pinfunction "C_C") (pintype "passive"))
      (node (ref "P4") (pin "21") (pinfunction "21_21") (pintype "bidirectional"))
    )
    (net (code "37") (name "/PREVGL") (class "Default")
      (node (ref "C47") (pin "1") (pinfunction "1_1") (pintype "passive"))
      (node (ref "D2") (pin "A") (pinfunction "A_A") (pintype "passive"))
      (node (ref "P4") (pin "23") (pinfunction "23_23") (pintype "bidirectional"))
    )
    (net (code "38") (name "/RESE") (class "Default")
      (node (ref "P4") (pin "3") (pinfunction "3_3") (pintype "bidirectional"))
      (node (ref "Q12") (pin "2") (pinfunction "S_2") (pintype "passive"))
      (node (ref "R5") (pin "1") (pinfunction "1_1") (pintype "passive"))
    )
    (net (code "39") (name "/RTS") (class "Default")
      (node (ref "Q2") (pin "2") (pinfunction "E_2") (pintype "passive"))
      (node (ref "R8") (pin "2") (pinfunction "2_2") (pintype "passive"))
      (node (ref "U8") (pin "6") (pinfunction "RTS#_6") (pintype "bidirectional"))
    )
    (net (code "40") (name "/RXD{slash}IO44") (class "Default")
      (node (ref "R79") (pin "1") (pinfunction "1_1") (pintype "passive"))
      (node (ref "RX") (pin "T") (pinfunction "T_T") (pintype "bidirectional"))
      (node (ref "U2") (pin "50") (pinfunction "U0RXD_50") (pintype "bidirectional"))
    )
    (net (code "41") (name "/SPICLK") (class "Default")
      (node (ref "R31") (pin "1") (pinfunction "1_1") (pintype "passive"))
      (node (ref "U3") (pin "6") (pinfunction "CLK_6") (pintype "bidirectional"))
    )
    (net (code "42") (name "/SPICS0") (class "Default")
      (node (ref "U2") (pin "32") (pinfunction "SPICS0_32") (pintype "bidirectional"))
      (node (ref "U3") (pin "1") (pinfunction "/CS_1") (pintype "bidirectional"))
    )
    (net (code "43") (name "/SPID") (class "Default")
      (node (ref "R29") (pin "1") (pinfunction "1_1") (pintype "passive"))
      (node (ref "U3") (pin "5") (pinfunction "DI(IO0)_5") (pintype "bidirectional"))
    )
    (net (code "44") (name "/SPIHD") (class "Default")
      (node (ref "R33") (pin "1") (pinfunction "1_1") (pintype "passive"))
      (node (ref "U3") (pin "7") (pinfunction "/HOLD/RESET(IO3)_7") (pintype "bidirectional"))
    )
    (net (code "45") (name "/SPIQ") (class "Default")
      (node (ref "R30") (pin "1") (pinfunction "1_1") (pintype "passive"))
      (node (ref "U3") (pin "2") (pinfunction "DO(IO1)_2") (pintype "bidirectional"))
    )
    (net (code "46") (name "/SPIWP") (class "Default")
      (node (ref "R32") (pin "1") (pinfunction "1_1") (pintype "passive"))
      (node (ref "U3") (pin "3") (pinfunction "/WP(IO2)_3") (pintype "bidirectional"))
    )
    (net (code "47") (name "/TXD{slash}IO43") (class "Default")
      (node (ref "R27") (pin "2") (pinfunction "2_2") (pintype "passive"))
      (node (ref "R80") (pin "1") (pinfunction "1_1") (pintype "passive"))
      (node (ref "TX") (pin "T") (pinfunction "T_T") (pintype "bidirectional"))
    )
    (net (code "48") (name "/USB_D+") (class "Default")
      (node (ref "R2") (pin "1") (pinfunction "1_1") (pintype "passive"))
      (node (ref "USB-NATIVE") (pin "A6") (pinfunction "D+_A6") (pintype "bidirectional"))
      (node (ref "USB-NATIVE") (pin "B6") (pinfunction "D+_B6") (pintype "bidirectional"))
    )
    (net (code "49") (name "/USB_D-") (class "Default")
      (node (ref "R21") (pin "1") (pinfunction "1_1") (pintype "passive"))
      (node (ref "USB-NATIVE") (pin "A7") (pinfunction "D-_A7") (pintype "bidirectional"))
      (node (ref "USB-NATIVE") (pin "B7") (pinfunction "D-_B7") (pintype "bidirectional"))
    )
    (net (code "50") (name "/VBAT-") (class "Default")
      (node (ref "BAT") (pin "-") (pinfunction "2_-") (pintype "bidirectional"))
      (node (ref "C5") (pin "2") (pinfunction "2_2") (pintype "passive"))
      (node (ref "R44") (pin "2") (pinfunction "2_2") (pintype "passive"))
      (node (ref "U4") (pin "3") (pinfunction "S2_3") (pintype "bidirectional"))
      (node (ref "U4") (pin "6") (pinfunction "VSS_6") (pintype "bidirectional"))
    )
    (net (code "51") (name "/VCOM") (class "Default")
      (node (ref "C46") (pin "1") (pinfunction "1_1") (pintype "passive"))
      (node (ref "P4") (pin "24") (pinfunction "24_24") (pintype "bidirectional"))
    )
    (net (code "52") (name "/VDD_SPI") (class "Default")
      (node (ref "C33") (pin "2") (pinfunction "2_2") (pintype "passive"))
      (node (ref "C35") (pin "2") (pinfunction "2_2") (pintype "passive"))
      (node (ref "U2") (pin "29") (pinfunction "VDD_SPI_29") (pintype "bidirectional"))
      (node (ref "U3") (pin "8") (pinfunction "VCC_8") (pintype "bidirectional"))
    )
    (net (code "53") (name "/VSYS") (class "Default")
      (node (ref "C42") (pin "2") (pinfunction "2_2") (pintype "passive"))
      (node (ref "D3") (pin "-") (pinfunction "-_-") (pintype "passive"))
      (node (ref "Q3") (pin "2") (pinfunction "S_2") (pintype "passive"))
      (node (ref "U5") (pin "1") (pinfunction "VIN_1") (pintype "bidirectional"))
      (node (ref "U5") (pin "3") (pinfunction "EN_3") (pintype "bidirectional"))
    )
    (net (code "54") (name "5V") (class "Default")
      (node (ref "C20") (pin "2") (pinfunction "2_2") (pintype "passive"))
      (node (ref "C54") (pin "1") (pinfunction "1_1") (pintype "passive"))
      (node (ref "C6") (pin "2") (pinfunction "2_2") (pintype "passive"))
      (node (ref "CHRG") (pin "A") (pinfunction "A_A") (pintype "passive"))
      (node (ref "D3") (pin "+") (pinfunction "+_+") (pintype "passive"))
      (node (ref "D6") (pin "-") (pinfunction "-_-") (pintype "passive"))
      (node (ref "DONE") (pin "A") (pinfunction "A_A") (pintype "passive"))
      (node (ref "Q3") (pin "1") (pinfunction "G_1") (pintype "passive"))
      (node (ref "R40") (pin "1") (pinfunction "1_1") (pintype "passive"))
      (node (ref "U1") (pin "4") (pinfunction "VIN_4") (pintype "bidirectional"))
      (node (ref "U1") (pin "8") (pinfunction "CE_8") (pintype "bidirectional"))
      (node (ref "USB-NATIVE") (pin "VBUS1") (pinfunction "VBUS_VBUS1") (pintype "bidirectional"))
      (node (ref "USB-NATIVE") (pin "VBUS2") (pinfunction "VBUS_VBUS2") (pintype "bidirectional"))
    )
    (net (code "55") (name "D+") (class "Default")
      (node (ref "U8") (pin "1") (pinfunction "UD+_1") (pintype "bidirectional"))
      (node (ref "USB-TTL") (pin "A6") (pinfunction "D+_A6") (pintype "bidirectional"))
      (node (ref "USB-TTL") (pin "B6") (pinfunction "D+_B6") (pintype "bidirectional"))
    )
    (net (code "56") (name "D-") (class "Default")
      (node (ref "U8") (pin "2") (pinfunction "UD-_2") (pintype "bidirectional"))
      (node (ref "USB-TTL") (pin "A7") (pinfunction "D-_A7") (pintype "bidirectional"))
      (node (ref "USB-TTL") (pin "B7") (pinfunction "D-_B7") (pintype "bidirectional"))
    )
    (net (code "57") (name "GND") (class "Default")
      (node (ref "ANT1") (pin "GND") (pinfunction "GND_GND") (pintype "passive"))
      (node (ref "BAT") (pin "3") (pinfunction "3_3") (pintype "bidirectional"))
      (node (ref "BAT") (pin "4") (pinfunction "4_4") (pintype "bidirectional"))
      (node (ref "C1") (pin "1") (pinfunction "1_1") (pintype "passive"))
      (node (ref "C10") (pin "1") (pinfunction "1_1") (pintype "passive"))
      (node (ref "C11") (pin "1") (pinfunction "1_1") (pintype "passive"))
      (node (ref "C12") (pin "1") (pinfunction "1_1") (pintype "passive"))
      (node (ref "C13") (pin "1") (pinfunction "1_1") (pintype "passive"))
      (node (ref "C14") (pin "1") (pinfunction "1_1") (pintype "passive"))
      (node (ref "C15") (pin "1") (pinfunction "1_1") (pintype "passive"))
      (node (ref "C17") (pin "1") (pinfunction "1_1") (pintype "passive"))
      (node (ref "C18") (pin "1") (pinfunction "1_1") (pintype "passive"))
      (node (ref "C19") (pin "1") (pinfunction "1_1") (pintype "passive"))
      (node (ref "C2") (pin "1") (pinfunction "1_1") (pintype "passive"))
      (node (ref "C20") (pin "1") (pinfunction "1_1") (pintype "passive"))
      (node (ref "C21") (pin "1") (pinfunction "1_1") (pintype "passive"))
      (node (ref "C22") (pin "2") (pinfunction "2_2") (pintype "passive"))
      (node (ref "C23") (pin "1") (pinfunction "1_1") (pintype "passive"))
      (node (ref "C24") (pin "1") (pinfunction "1_1") (pintype "passive"))
      (node (ref "C25") (pin "1") (pinfunction "1_1") (pintype "passive"))
      (node (ref "C26") (pin "1") (pinfunction "1_1") (pintype "passive"))
      (node (ref "C27") (pin "1") (pinfunction "1_1") (pintype "passive"))
      (node (ref "C28") (pin "1") (pinfunction "1_1") (pintype "passive"))
      (node (ref "C29") (pin "1") (pinfunction "1_1") (pintype "passive"))
      (node (ref "C3") (pin "1") (pinfunction "1_1") (pintype "passive"))
      (node (ref "C30") (pin "1") (pinfunction "1_1") (pintype "passive"))
      (node (ref "C31") (pin "1") (pinfunction "1_1") (pintype "passive"))
      (node (ref "C32") (pin "1") (pinfunction "1_1") (pintype "passive"))
      (node (ref "C33") (pin "1") (pinfunction "1_1") (pintype "passive"))
      (node (ref "C34") (pin "1") (pinfunction "1_1") (pintype "passive"))
      (node (ref "C35") (pin "1") (pinfunction "1_1") (pintype "passive"))
      (node (ref "C36") (pin "1") (pinfunction "1_1") (pintype "passive"))
      (node (ref "C38") (pin "2") (pinfunction "2_2") (pintype "passive"))
      (node (ref "C39") (pin "2") (pinfunction "2_2") (pintype "passive"))
      (node (ref "C4") (pin "2") (pinfunction "2_2") (pintype "passive"))
      (node (ref "C40") (pin "2") (pinfunction "2_2") (pintype "passive"))
      (node (ref "C41") (pin "1") (pinfunction "1_1") (pintype "passive"))
      (node (ref "C42") (pin "1") (pinfunction "1_1") (pintype "passive"))
      (node (ref "C43") (pin "2") (pinfunction "2_2") (pintype "passive"))
      (node (ref "C44") (pin "2") (pinfunction "2_2") (pintype "passive"))
      (node (ref "C45") (pin "2") (pinfunction "2_2") (pintype "passive"))
      (node (ref "C46") (pin "2") (pinfunction "2_2") (pintype "passive"))
      (node (ref "C47") (pin "2") (pinfunction "2_2") (pintype "passive"))
      (node (ref "C49") (pin "2") (pinfunction "2_2") (pintype "passive"))
      (node (ref "C50") (pin "2") (pinfunction "2_2") (pintype "passive"))
      (node (ref "C51") (pin "2") (pinfunction "2_2") (pintype "passive"))
      (node (ref "C52") (pin "1") (pinfunction "1_1") (pintype "passive"))
      (node (ref "C53") (pin "2") (pinfunction "2_2") (pintype "passive"))
      (node (ref "C54") (pin "2") (pinfunction "2_2") (pintype "passive"))
      (node (ref "C55") (pin "1") (pinfunction "1_1") (pintype "passive"))
      (node (ref "C57") (pin "1") (pinfunction "1_1") (pintype "passive"))
      (node (ref "C6") (pin "1") (pinfunction "1_1") (pintype "passive"))
      (node (ref "C8") (pin "1") (pinfunction "1_1") (pintype "passive"))
      (node (ref "C9") (pin "1") (pinfunction "1_1") (pintype "passive"))
      (node (ref "D4") (pin "C") (pinfunction "C_C") (pintype "passive"))
      (node (ref "D5") (pin "2") (pinfunction "A_2") (pintype "passive"))
      (node (ref "FLASH") (pin "1") (pinfunction "1_1") (pintype "bidirectional"))
      (node (ref "FLASH") (pin "3") (pinfunction "3_3") (pintype "bidirectional"))
      (node (ref "FLASH") (pin "4") (pinfunction "4_4") (pintype "bidirectional"))
      (node (ref "G") (pin "T") (pinfunction "T_T") (pintype "bidirectional"))
      (node (ref "GND") (pin "T") (pinfunction "T_T") (pintype "bidirectional"))
      (node (ref "J1") (pin "4") (pinfunction "4_4") (pintype "bidirectional"))
      (node (ref "J1") (pin "SS1") (pinfunction "SS1_SS1") (pintype "bidirectional"))
      (node (ref "J1") (pin "SS2") (pinfunction "SS2_SS2") (pintype "bidirectional"))
      (node (ref "J2") (pin "4") (pinfunction "4_4") (pintype "bidirectional"))
      (node (ref "J2") (pin "SS1") (pinfunction "SS1_SS1") (pintype "bidirectional"))
      (node (ref "J2") (pin "SS2") (pinfunction "SS2_SS2") (pintype "bidirectional"))
      (node (ref "M1") (pin "1") (pinfunction "P$1_1") (pintype "bidirectional"))
      (node (ref "M2") (pin "1") (pinfunction "P$1_1") (pintype "bidirectional"))
      (node (ref "M3") (pin "1") (pinfunction "P$1_1") (pintype "bidirectional"))
      (node (ref "M4") (pin "1") (pinfunction "P$1_1") (pintype "bidirectional"))
      (node (ref "M5") (pin "1") (pinfunction "P$1_1") (pintype "bidirectional"))
      (node (ref "M6") (pin "1") (pinfunction "P$1_1") (pintype "bidirectional"))
      (node (ref "M7") (pin "1") (pinfunction "P$1_1") (pintype "bidirectional"))
      (node (ref "M8") (pin "1") (pinfunction "P$1_1") (pintype "bidirectional"))
      (node (ref "P1") (pin "6") (pinfunction "6_6") (pintype "bidirectional"))
      (node (ref "P1") (pin "7") (pinfunction "7_7") (pintype "bidirectional"))
      (node (ref "P1") (pin "8") (pinfunction "8_8") (pintype "bidirectional"))
      (node (ref "P4") (pin "17") (pinfunction "17_17") (pintype "bidirectional"))
      (node (ref "P4") (pin "25") (pinfunction "25_25") (pintype "bidirectional"))
      (node (ref "P4") (pin "26") (pinfunction "26_26") (pintype "bidirectional"))
      (node (ref "P4") (pin "8") (pinfunction "8_8") (pintype "bidirectional"))
      (node (ref "Q7") (pin "2") (pinfunction "S_2") (pintype "passive"))
      (node (ref "R17") (pin "1") (pinfunction "1_1") (pintype "passive"))
      (node (ref "R19") (pin "1") (pinfunction "1_1") (pintype "passive"))
      (node (ref "R25") (pin "1") (pinfunction "1_1") (pintype "passive"))
      (node (ref "R3") (pin "1") (pinfunction "1_1") (pintype "passive"))
      (node (ref "R36") (pin "1") (pinfunction "1_1") (pintype "passive"))
      (node (ref "R37") (pin "2") (pinfunction "2_2") (pintype "passive"))
      (node (ref "R40") (pin "2") (pinfunction "2_2") (pintype "passive"))
      (node (ref "R43") (pin "1") (pinfunction "1_1") (pintype "passive"))
      (node (ref "R44") (pin "1") (pinfunction "1_1") (pintype "passive"))
      (node (ref "R46") (pin "1") (pinfunction "1_1") (pintype "passive"))
      (node (ref "R5") (pin "2") (pinfunction "2_2") (pintype "passive"))
      (node (ref "R6") (pin "2") (pinfunction "2_2") (pintype "passive"))
      (node (ref "R72") (pin "1") (pinfunction "1_1") (pintype "passive"))
      (node (ref "RST") (pin "1") (pinfunction "1_1") (pintype "bidirectional"))
      (node (ref "RST") (pin "3") (pinfunction "3_3") (pintype "bidirectional"))
      (node (ref "RST") (pin "4") (pinfunction "4_4") (pintype "bidirectional"))
      (node (ref "SD") (pin "6") (pinfunction "VSS_6") (pintype "bidirectional"))
      (node (ref "SD") (pin "G1") (pinfunction "G1_G1") (pintype "bidirectional"))
      (node (ref "SD") (pin "G2") (pinfunction "G2_G2") (pintype "bidirectional"))
      (node (ref "SD") (pin "G3") (pinfunction "G3_G3") (pintype "bidirectional"))
      (node (ref "SD") (pin "G4") (pinfunction "G4_G4") (pintype "bidirectional"))
      (node (ref "SW1") (pin "3") (pinfunction "3_3") (pintype "bidirectional"))
      (node (ref "SW1") (pin "C") (pinfunction "C_C") (pintype "bidirectional"))
      (node (ref "SW2") (pin "3") (pinfunction "3_3") (pintype "bidirectional"))
      (node (ref "SW2") (pin "C") (pinfunction "C_C") (pintype "bidirectional"))
      (node (ref "U1") (pin "1") (pinfunction "TEMP_1") (pintype "bidirectional"))
      (node (ref "U1") (pin "3") (pinfunction "GND_3") (pintype "bidirectional"))
      (node (ref "U1") (pin "9") (pinfunction "GND_9") (pintype "bidirectional"))
      (node (ref "U2") (pin "57") (pinfunction "GND_57") (pintype "bidirectional"))
      (node (ref "U3") (pin "4") (pinfunction "GND_4") (pintype "bidirectional"))
      (node (ref "U4") (pin "2") (pinfunction "S1_2") (pintype "bidirectional"))
      (node (ref "U5") (pin "2") (pinfunction "GND_2") (pintype "bidirectional"))
      (node (ref "U8") (pin "3") (pinfunction "GND_3") (pintype "bidirectional"))
      (node (ref "U8") (pin "EP") (pinfunction "EP_EP") (pintype "bidirectional"))
      (node (ref "USB-NATIVE") (pin "GND") (pinfunction "GND_GND") (pintype "bidirectional"))
      (node (ref "USB-NATIVE") (pin "GND2") (pinfunction "GND_GND2") (pintype "bidirectional"))
      (node (ref "USB-NATIVE") (pin "SHLD1") (pinfunction "SHLD_SHLD1") (pintype "bidirectional"))
      (node (ref "USB-NATIVE") (pin "SHLD2") (pinfunction "SHLD_SHLD2") (pintype "bidirectional"))
      (node (ref "USB-NATIVE") (pin "SHLD3") (pinfunction "SHLD_SHLD3") (pintype "bidirectional"))
      (node (ref "USB-NATIVE") (pin "SHLD4") (pinfunction "SHLD_SHLD4") (pintype "bidirectional"))
      (node (ref "USB-NATIVE") (pin "SHLD5") (pinfunction "SHLD_SHLD5") (pintype "bidirectional"))
      (node (ref "USB-NATIVE") (pin "SHLD6") (pinfunction "SHLD_SHLD6") (pintype "bidirectional"))
      (node (ref "USB-NATIVE") (pin "SHLD7") (pinfunction "SHLD_SHLD7") (pintype "bidirectional"))
      (node (ref "USB-NATIVE") (pin "SHLD8") (pinfunction "SHLD_SHLD8") (pintype "bidirectional"))
      (node (ref "USB-TTL") (pin "GND") (pinfunction "GND_GND") (pintype "bidirectional"))
      (node (ref "USB-TTL") (pin "GND2") (pinfunction "GND_GND2") (pintype "bidirectional"))
      (node (ref "USB-TTL") (pin "SHLD1") (pinfunction "SHLD_SHLD1") (pintype "bidirectional"))
      (node (ref "USB-TTL") (pin "SHLD2") (pinfunction "SHLD_SHLD2") (pintype "bidirectional"))
      (node (ref "USB-TTL") (pin "SHLD3") (pinfunction "SHLD_SHLD3") (pintype "bidirectional"))
      (node (ref "USB-TTL") (pin "SHLD4") (pinfunction "SHLD_SHLD4") (pintype "bidirectional"))
      (node (ref "USB-TTL") (pin "SHLD5") (pinfunction "SHLD_SHLD5") (pintype "bidirectional"))
      (node (ref "USB-TTL") (pin "SHLD6") (pinfunction "SHLD_SHLD6") (pintype "bidirectional"))
      (node (ref "USB-TTL") (pin "SHLD7") (pinfunction "SHLD_SHLD7") (pintype "bidirectional"))
      (node (ref "USB-TTL") (pin "SHLD8") (pinfunction "SHLD_SHLD8") (pintype "bidirectional"))
      (node (ref "X1") (pin "2") (pinfunction "G2_2") (pintype "power_in"))
      (node (ref "X1") (pin "4") (pinfunction "G1_4") (pintype "power_in"))
    )
    (net (code "58") (name "Net-(ANT-Pad2)") (class "Default")
      (node (ref "ANT") (pin "2") (pinfunction "2_2") (pintype "passive"))
      (node (ref "R15") (pin "2") (pinfunction "2_2") (pintype "passive"))
    )
    (net (code "59") (name "Net-(ANT1-PadFEED)") (class "Default")
      (node (ref "ANT1") (pin "FEED") (pinfunction "FEED_FEED") (pintype "passive"))
      (node (ref "R1") (pin "1") (pinfunction "1_1") (pintype "passive"))
    )
    (net (code "60") (name "Net-(C12-Pad2)") (class "Default")
      (node (ref "C12") (pin "2") (pinfunction "2_2") (pintype "passive"))
      (node (ref "L2") (pin "1") (pinfunction "1_1") (pintype "passive"))
      (node (ref "L4") (pin "2") (pinfunction "2_2") (pintype "passive"))
      (node (ref "R1") (pin "2") (pinfunction "2_2") (pintype "passive"))
      (node (ref "R15") (pin "1") (pinfunction "1_1") (pintype "passive"))
    )
    (net (code "61") (name "Net-(C14-Pad2)") (class "Default")
      (node (ref "C14") (pin "2") (pinfunction "2_2") (pintype "passive"))
      (node (ref "L4") (pin "1") (pinfunction "1_1") (pintype "passive"))
    )
    (net (code "62") (name "Net-(C19-Pad2)") (class "Default")
      (node (ref "C19") (pin "2") (pinfunction "2_2") (pintype "passive"))
      (node (ref "L1") (pin "2") (pinfunction "2_2") (pintype "passive"))
      (node (ref "U2") (pin "2") (pinfunction "VDD3P3_2") (pintype "bidirectional"))
      (node (ref "U2") (pin "3") (pinfunction "VDD3P3_3") (pintype "bidirectional"))
    )
    (net (code "63") (name "Net-(C38-Pad1)") (class "Default")
      (node (ref "C38") (pin "1") (pinfunction "1_1") (pintype "passive"))
      (node (ref "P4") (pin "5") (pinfunction "5_5") (pintype "bidirectional"))
    )
    (net (code "64") (name "Net-(C40-Pad1)") (class "Default")
      (node (ref "C40") (pin "1") (pinfunction "1_1") (pintype "passive"))
      (node (ref "P4") (pin "18") (pinfunction "18_18") (pintype "bidirectional"))
    )
    (net (code "65") (name "Net-(C43-Pad1)") (class "Default")
      (node (ref "C43") (pin "1") (pinfunction "1_1") (pintype "passive"))
      (node (ref "P4") (pin "19") (pinfunction "19_19") (pintype "bidirectional"))
    )
    (net (code "66") (name "Net-(C44-Pad1)") (class "Default")
      (node (ref "C44") (pin "1") (pinfunction "1_1") (pintype "passive"))
      (node (ref "P4") (pin "20") (pinfunction "20_20") (pintype "bidirectional"))
    )
    (net (code "67") (name "Net-(C45-Pad1)") (class "Default")
      (node (ref "C45") (pin "1") (pinfunction "1_1") (pintype "passive"))
      (node (ref "P4") (pin "22") (pinfunction "22_22") (pintype "bidirectional"))
    )
    (net (code "68") (name "Net-(C48-Pad1)") (class "Default")
      (node (ref "C48") (pin "1") (pinfunction "1_1") (pintype "passive"))
      (node (ref "D2") (pin "C") (pinfunction "C_C") (pintype "passive"))
      (node (ref "D4") (pin "A") (pinfunction "A_A") (pintype "passive"))
    )
    (net (code "69") (name "Net-(CHRG-PadC)") (class "Default")
      (node (ref "CHRG") (pin "C") (pinfunction "C_C") (pintype "passive"))
      (node (ref "R38") (pin "1") (pinfunction "1_1") (pintype "passive"))
    )
    (net (code "70") (name "Net-(D5-C1)") (class "Default")
      (node (ref "D5") (pin "1") (pinfunction "C1_1") (pintype "passive"))
      (node (ref "R71") (pin "1") (pinfunction "1_1") (pintype "passive"))
      (node (ref "SD") (pin "2") (pinfunction "CS_2") (pintype "bidirectional"))
    )
    (net (code "71") (name "Net-(DONE-PadC)") (class "Default")
      (node (ref "DONE") (pin "C") (pinfunction "C_C") (pintype "passive"))
      (node (ref "R39") (pin "1") (pinfunction "1_1") (pintype "passive"))
    )
    (net (code "72") (name "Net-(L3-2)") (class "Default")
      (node (ref "C48") (pin "2") (pinfunction "2_2") (pintype "passive"))
      (node (ref "D1") (pin "A") (pinfunction "A_A") (pintype "passive"))
      (node (ref "L3") (pin "P$2") (pinfunction "2_P$2") (pintype "passive"))
      (node (ref "Q12") (pin "3") (pinfunction "D_3") (pintype "passive"))
    )
    (net (code "73") (name "Net-(PWR-PadC)") (class "Default")
      (node (ref "PWR") (pin "C") (pinfunction "C_C") (pintype "passive"))
      (node (ref "R25") (pin "2") (pinfunction "2_2") (pintype "passive"))
    )
    (net (code "74") (name "Net-(Q2-B)") (class "Default")
      (node (ref "Q2") (pin "1") (pinfunction "B_1") (pintype "passive"))
      (node (ref "R9") (pin "1") (pinfunction "1_1") (pintype "passive"))
    )
    (net (code "75") (name "Net-(Q5-B)") (class "Default")
      (node (ref "Q5") (pin "1") (pinfunction "B_1") (pintype "passive"))
      (node (ref "R8") (pin "1") (pinfunction "1_1") (pintype "passive"))
    )
    (net (code "76") (name "Net-(Q6-D)") (class "Default")
      (node (ref "Q6") (pin "3") (pinfunction "D_3") (pintype "passive"))
      (node (ref "R12") (pin "2") (pinfunction "2_2") (pintype "passive"))
    )
    (net (code "77") (name "Net-(Q6-G)") (class "Default")
      (node (ref "C16") (pin "1") (pinfunction "1_1") (pintype "passive"))
      (node (ref "Q6") (pin "1") (pinfunction "G_1") (pintype "passive"))
      (node (ref "R11") (pin "2") (pinfunction "2_2") (pintype "passive"))
    )
    (net (code "78") (name "Net-(Q7-D)") (class "Default")
      (node (ref "Q7") (pin "3") (pinfunction "D_3") (pintype "passive"))
      (node (ref "R11") (pin "1") (pinfunction "1_1") (pintype "passive"))
      (node (ref "R14") (pin "1") (pinfunction "1_1") (pintype "passive"))
    )
    (net (code "79") (name "Net-(Q7-G)") (class "Default")
      (node (ref "Q7") (pin "1") (pinfunction "G_1") (pintype "passive"))
      (node (ref "R17") (pin "2") (pinfunction "2_2") (pintype "passive"))
      (node (ref "R24") (pin "1") (pinfunction "1_1") (pintype "passive"))
    )
    (net (code "80") (name "Net-(SD-DATA1)") (class "Default")
      (node (ref "R70") (pin "1") (pinfunction "1_1") (pintype "passive"))
      (node (ref "SD") (pin "8") (pinfunction "DATA1_8") (pintype "bidirectional"))
    )
    (net (code "81") (name "Net-(SD-DATA2)") (class "Default")
      (node (ref "R10") (pin "1") (pinfunction "1_1") (pintype "passive"))
      (node (ref "SD") (pin "1") (pinfunction "DATA2_1") (pintype "bidirectional"))
    )
    (net (code "82") (name "Net-(U1-CHRG)") (class "Default")
      (node (ref "R38") (pin "2") (pinfunction "2_2") (pintype "passive"))
      (node (ref "U1") (pin "7") (pinfunction "CHRG_7") (pintype "bidirectional"))
    )
    (net (code "83") (name "Net-(U1-DONE)") (class "Default")
      (node (ref "R39") (pin "2") (pinfunction "2_2") (pintype "passive"))
      (node (ref "U1") (pin "6") (pinfunction "DONE_6") (pintype "bidirectional"))
    )
    (net (code "84") (name "Net-(U1-ISET)") (class "Default")
      (node (ref "R37") (pin "1") (pinfunction "1_1") (pintype "passive"))
      (node (ref "U1") (pin "2") (pinfunction "ISET_2") (pintype "bidirectional"))
    )
    (net (code "85") (name "Net-(U2-LNA_IN)") (class "Default")
      (node (ref "C13") (pin "2") (pinfunction "2_2") (pintype "passive"))
      (node (ref "L2") (pin "2") (pinfunction "2_2") (pintype "passive"))
      (node (ref "U2") (pin "1") (pinfunction "LNA_IN_1") (pintype "bidirectional"))
    )
    (net (code "86") (name "Net-(U2-SPICLK)") (class "Default")
      (node (ref "R31") (pin "2") (pinfunction "2_2") (pintype "passive"))
      (node (ref "U2") (pin "33") (pinfunction "SPICLK_33") (pintype "bidirectional"))
    )
    (net (code "87") (name "Net-(U2-SPID)") (class "Default")
      (node (ref "R29") (pin "2") (pinfunction "2_2") (pintype "passive"))
      (node (ref "U2") (pin "35") (pinfunction "SPID_35") (pintype "bidirectional"))
    )
    (net (code "88") (name "Net-(U2-SPIHD)") (class "Default")
      (node (ref "R33") (pin "2") (pinfunction "2_2") (pintype "passive"))
      (node (ref "U2") (pin "30") (pinfunction "SPIHD_30") (pintype "bidirectional"))
    )
    (net (code "89") (name "Net-(U2-SPIQ)") (class "Default")
      (node (ref "R30") (pin "2") (pinfunction "2_2") (pintype "passive"))
      (node (ref "U2") (pin "34") (pinfunction "SPIQ_34") (pintype "bidirectional"))
    )
    (net (code "90") (name "Net-(U2-SPIWP)") (class "Default")
      (node (ref "R32") (pin "2") (pinfunction "2_2") (pintype "passive"))
      (node (ref "U2") (pin "31") (pinfunction "SPIWP_31") (pintype "bidirectional"))
    )
    (net (code "91") (name "Net-(U2-U0TXD)") (class "Default")
      (node (ref "R27") (pin "1") (pinfunction "1_1") (pintype "passive"))
      (node (ref "U2") (pin "49") (pinfunction "U0TXD_49") (pintype "bidirectional"))
    )
    (net (code "92") (name "Net-(U2-XTAL_N)") (class "Default")
      (node (ref "C9") (pin "2") (pinfunction "2_2") (pintype "passive"))
      (node (ref "U2") (pin "53") (pinfunction "XTAL_N_53") (pintype "bidirectional"))
      (node (ref "X1") (pin "3") (pinfunction "X2_3") (pintype "bidirectional"))
    )
    (net (code "93") (name "Net-(U2-XTAL_P)") (class "Default")
      (node (ref "R26") (pin "1") (pinfunction "1_1") (pintype "passive"))
      (node (ref "U2") (pin "54") (pinfunction "XTAL_P_54") (pintype "bidirectional"))
    )
    (net (code "94") (name "Net-(U4-V)") (class "Default")
      (node (ref "R43") (pin "2") (pinfunction "2_2") (pintype "passive"))
      (node (ref "U4") (pin "1") (pinfunction "V_1") (pintype "bidirectional"))
    )
    (net (code "95") (name "Net-(U4-VDD)") (class "Default")
      (node (ref "C5") (pin "1") (pinfunction "1_1") (pintype "passive"))
      (node (ref "R45") (pin "2") (pinfunction "2_2") (pintype "passive"))
      (node (ref "U4") (pin "5") (pinfunction "VDD_5") (pintype "bidirectional"))
    )
    (net (code "96") (name "Net-(U5-BYP)") (class "Default")
      (node (ref "C11") (pin "2") (pinfunction "2_2") (pintype "passive"))
      (node (ref "U5") (pin "4") (pinfunction "BYP_4") (pintype "bidirectional"))
    )
    (net (code "97") (name "Net-(U8-RXD)") (class "Default")
      (node (ref "R80") (pin "2") (pinfunction "2_2") (pintype "passive"))
      (node (ref "U8") (pin "9") (pinfunction "RXD_9") (pintype "bidirectional"))
    )
    (net (code "98") (name "Net-(U8-TXD)") (class "Default")
      (node (ref "R79") (pin "2") (pinfunction "2_2") (pintype "passive"))
      (node (ref "U8") (pin "8") (pinfunction "TXD_8") (pintype "bidirectional"))
    )
    (net (code "99") (name "Net-(USB-NATIVE-CC1)") (class "Default")
      (node (ref "R3") (pin "2") (pinfunction "2_2") (pintype "passive"))
      (node (ref "USB-NATIVE") (pin "A5") (pinfunction "CC1_A5") (pintype "bidirectional"))
    )
    (net (code "100") (name "Net-(USB-NATIVE-CC2)") (class "Default")
      (node (ref "R36") (pin "2") (pinfunction "2_2") (pintype "passive"))
      (node (ref "USB-NATIVE") (pin "B5") (pinfunction "CC2_B5") (pintype "bidirectional"))
    )
    (net (code "101") (name "Net-(USB-TTL-CC1)") (class "Default")
      (node (ref "R46") (pin "2") (pinfunction "2_2") (pintype "passive"))
      (node (ref "USB-TTL") (pin "A5") (pinfunction "CC1_A5") (pintype "bidirectional"))
    )
    (net (code "102") (name "Net-(USB-TTL-CC2)") (class "Default")
      (node (ref "R72") (pin "2") (pinfunction "2_2") (pintype "passive"))
      (node (ref "USB-TTL") (pin "B5") (pinfunction "CC2_B5") (pintype "bidirectional"))
    )
    (net (code "103") (name "Net-(X1-X1)") (class "Default")
      (node (ref "C4") (pin "1") (pinfunction "1_1") (pintype "passive"))
      (node (ref "R26") (pin "2") (pinfunction "2_2") (pintype "passive"))
      (node (ref "X1") (pin "1") (pinfunction "X1_1") (pintype "bidirectional"))
    )
    (net (code "104") (name "VBAT+") (class "Default")
      (node (ref "BAT") (pin "+") (pinfunction "1_+") (pintype "bidirectional"))
      (node (ref "C1") (pin "2") (pinfunction "2_2") (pintype "passive"))
      (node (ref "C16") (pin "2") (pinfunction "2_2") (pintype "passive"))
      (node (ref "C2") (pin "2") (pinfunction "2_2") (pintype "passive"))
      (node (ref "C53") (pin "1") (pinfunction "1_1") (pintype "passive"))
      (node (ref "Q3") (pin "3") (pinfunction "D_3") (pintype "passive"))
      (node (ref "Q6") (pin "2") (pinfunction "S_2") (pintype "passive"))
      (node (ref "R14") (pin "2") (pinfunction "2_2") (pintype "passive"))
      (node (ref "R45") (pin "1") (pinfunction "1_1") (pintype "passive"))
      (node (ref "U1") (pin "5") (pinfunction "BAT_5") (pintype "bidirectional"))
    )
    (net (code "105") (name "VBUS") (class "Default")
      (node (ref "C29") (pin "2") (pinfunction "2_2") (pintype "passive"))
      (node (ref "C30") (pin "2") (pinfunction "2_2") (pintype "passive"))
      (node (ref "C34") (pin "2") (pinfunction "2_2") (pintype "passive"))
      (node (ref "D6") (pin "+") (pinfunction "+_+") (pintype "passive"))
      (node (ref "USB-TTL") (pin "VBUS1") (pinfunction "VBUS_VBUS1") (pintype "bidirectional"))
      (node (ref "USB-TTL") (pin "VBUS2") (pinfunction "VBUS_VBUS2") (pintype "bidirectional"))
    )
    (net (code "106") (name "unconnected-(ANT-Pad1)") (class "Default")
      (node (ref "ANT") (pin "1") (pinfunction "1_1") (pintype "passive"))
    )
    (net (code "107") (name "unconnected-(P4-Pad1)") (class "Default")
      (node (ref "P4") (pin "1") (pinfunction "1_1") (pintype "bidirectional"))
    )
    (net (code "108") (name "unconnected-(P4-Pad4)") (class "Default")
      (node (ref "P4") (pin "4") (pinfunction "4_4") (pintype "bidirectional"))
    )
    (net (code "109") (name "unconnected-(P4-Pad6)") (class "Default")
      (node (ref "P4") (pin "6") (pinfunction "6_6") (pintype "bidirectional"))
    )
    (net (code "110") (name "unconnected-(P4-Pad7)") (class "Default")
      (node (ref "P4") (pin "7") (pinfunction "7_7") (pintype "bidirectional"))
    )
    (net (code "111") (name "unconnected-(SD-CDN-Pad9)") (class "Default")
      (node (ref "SD") (pin "9") (pinfunction "CDN_9") (pintype "bidirectional"))
    )
    (net (code "112") (name "unconnected-(U2-GPIO33-Pad38)") (class "Default")
      (node (ref "U2") (pin "38") (pinfunction "GPIO33_38") (pintype "bidirectional"))
    )
    (net (code "113") (name "unconnected-(U2-GPIO34-Pad39)") (class "Default")
      (node (ref "U2") (pin "39") (pinfunction "GPIO34_39") (pintype "bidirectional"))
    )
    (net (code "114") (name "unconnected-(U2-GPIO35-Pad40)") (class "Default")
      (node (ref "U2") (pin "40") (pinfunction "GPIO35_40") (pintype "bidirectional"))
    )
    (net (code "115") (name "unconnected-(U2-GPIO36-Pad41)") (class "Default")
      (node (ref "U2") (pin "41") (pinfunction "GPIO36_41") (pintype "bidirectional"))
    )
    (net (code "116") (name "unconnected-(U2-GPIO37-Pad42)") (class "Default")
      (node (ref "U2") (pin "42") (pinfunction "GPIO37_42") (pintype "bidirectional"))
    )
    (net (code "117") (name "unconnected-(U2-SPICS1-Pad28)") (class "Default")
      (node (ref "U2") (pin "28") (pinfunction "SPICS1_28") (pintype "bidirectional"))
    )
    (net (code "118") (name "unconnected-(U4-D-Pad4)") (class "Default")
      (node (ref "U4") (pin "4") (pinfunction "D_4") (pintype "bidirectional"))
    )
    (net (code "119") (name "unconnected-(U8-CTS#-Pad5)") (class "Default")
      (node (ref "U8") (pin "5") (pinfunction "CTS#_5") (pintype "bidirectional"))
    )
  )
)
